# MB_CPU_memory.net
KiCad netlist of a schematic drawn in Altium Designer
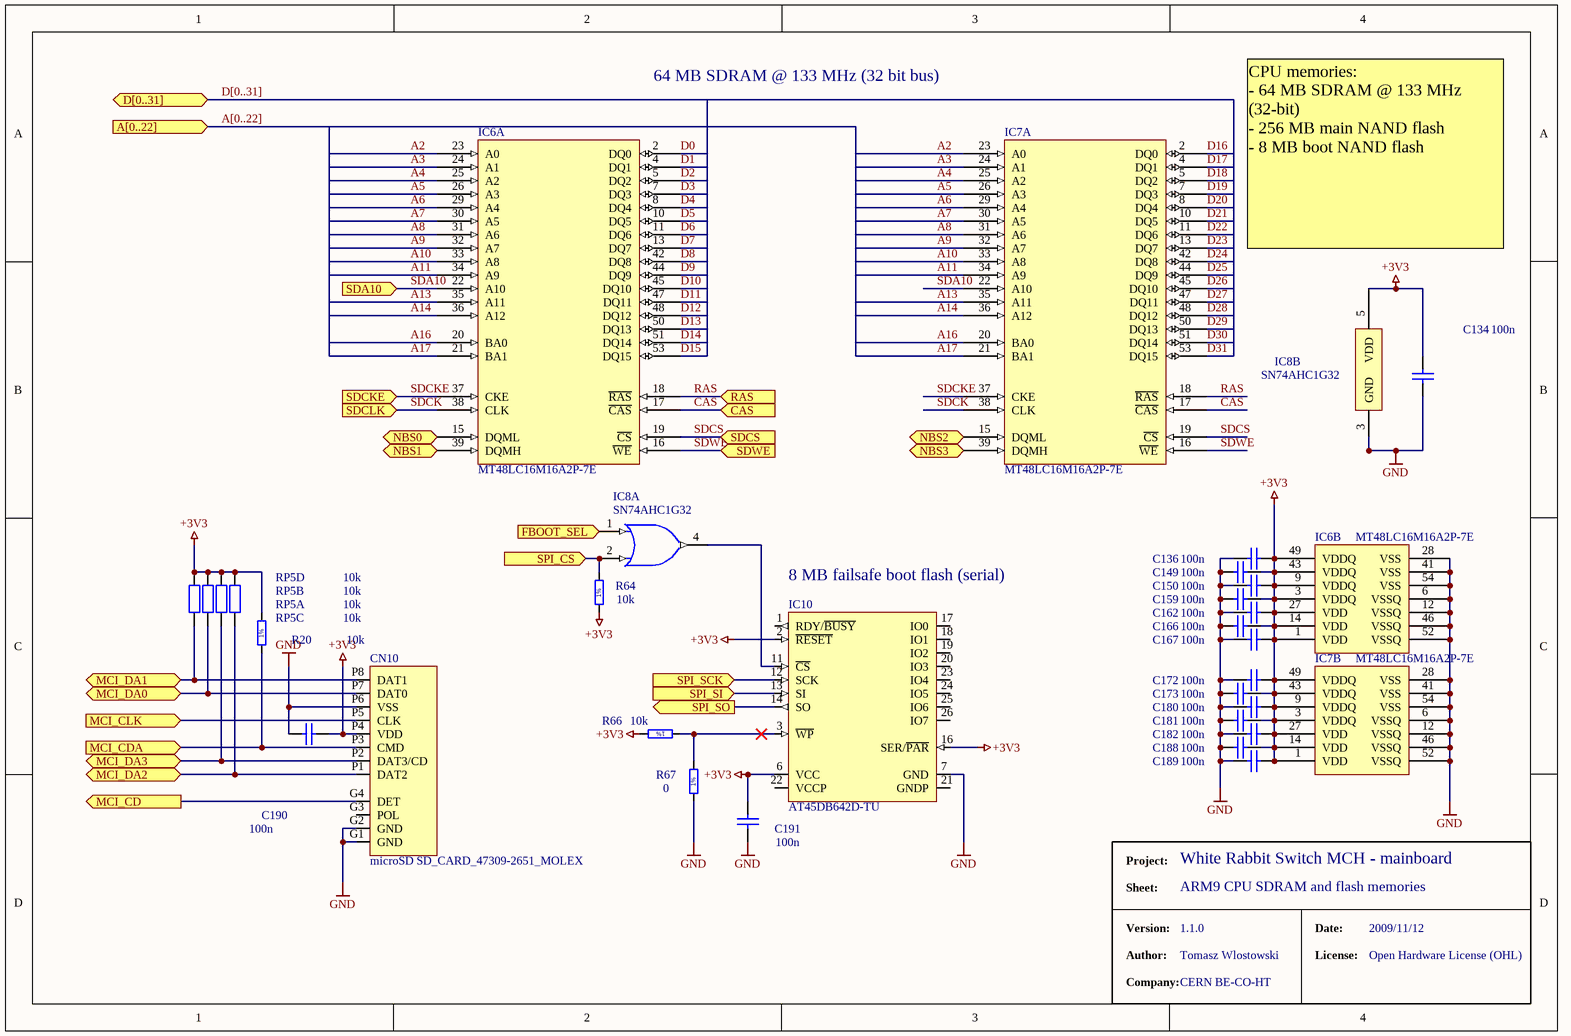
[diagram p0: MB_CPU_memory.SchDoc]

(export (version "E")
  (design (tool "Eeschema 10.0.6"))
  (components
    (comp (ref "C134")
      (value "100n")
      (footprint "CAPC1005X55N")
      (description "Non-polarised capacitor")
      (fields
        (field (name "PART NUMBER") "CC0402_100NF_16V_10%_X7R")
        (field (name "VOLTAGE") "16V")
        (field (name "AUTHOR") "CERN DEM JLC")
      )
      (libsource (lib "Capacitors") (part "Capacitor - non polarized"))
    )
    (comp (ref "C136")
      (value "100n")
      (footprint "CAPC1005X55N")
      (description "Non-polarised capacitor")
      (fields
        (field (name "PART NUMBER") "CC0402_100NF_16V_10%_X7R")
        (field (name "VOLTAGE") "16V")
        (field (name "AUTHOR") "CERN DEM JLC")
      )
      (libsource (lib "Capacitors") (part "Capacitor - non polarized"))
    )
    (comp (ref "C149")
      (value "100n")
      (footprint "CAPC1005X55N")
      (description "Non-polarised capacitor")
      (fields
        (field (name "PART NUMBER") "CC0402_100NF_16V_10%_X7R")
        (field (name "VOLTAGE") "16V")
        (field (name "AUTHOR") "CERN DEM JLC")
      )
      (libsource (lib "Capacitors") (part "Capacitor - non polarized"))
    )
    (comp (ref "C150")
      (value "100n")
      (footprint "CAPC1005X55N")
      (description "Non-polarised capacitor")
      (fields
        (field (name "PART NUMBER") "CC0402_100NF_16V_10%_X7R")
        (field (name "VOLTAGE") "16V")
        (field (name "AUTHOR") "CERN DEM JLC")
      )
      (libsource (lib "Capacitors") (part "Capacitor - non polarized"))
    )
    (comp (ref "C159")
      (value "100n")
      (footprint "CAPC1005X55N")
      (description "Non-polarised capacitor")
      (fields
        (field (name "PART NUMBER") "CC0402_100NF_16V_10%_X7R")
        (field (name "VOLTAGE") "16V")
        (field (name "AUTHOR") "CERN DEM JLC")
      )
      (libsource (lib "Capacitors") (part "Capacitor - non polarized"))
    )
    (comp (ref "C162")
      (value "100n")
      (footprint "CAPC1005X55N")
      (description "Non-polarised capacitor")
      (fields
        (field (name "PART NUMBER") "CC0402_100NF_16V_10%_X7R")
        (field (name "VOLTAGE") "16V")
        (field (name "AUTHOR") "CERN DEM JLC")
      )
      (libsource (lib "Capacitors") (part "Capacitor - non polarized"))
    )
    (comp (ref "C166")
      (value "100n")
      (footprint "CAPC1005X55N")
      (description "Non-polarised capacitor")
      (fields
        (field (name "PART NUMBER") "CC0402_100NF_16V_10%_X7R")
        (field (name "VOLTAGE") "16V")
        (field (name "AUTHOR") "CERN DEM JLC")
      )
      (libsource (lib "Capacitors") (part "Capacitor - non polarized"))
    )
    (comp (ref "C167")
      (value "100n")
      (footprint "CAPC1005X55N")
      (description "Non-polarised capacitor")
      (fields
        (field (name "PART NUMBER") "CC0402_100NF_16V_10%_X7R")
        (field (name "VOLTAGE") "16V")
        (field (name "AUTHOR") "CERN DEM JLC")
      )
      (libsource (lib "Capacitors") (part "Capacitor - non polarized"))
    )
    (comp (ref "C172")
      (value "100n")
      (footprint "CAPC1005X55N")
      (description "Non-polarised capacitor")
      (fields
        (field (name "PART NUMBER") "CC0402_100NF_16V_10%_X7R")
        (field (name "VOLTAGE") "16V")
        (field (name "AUTHOR") "CERN DEM JLC")
      )
      (libsource (lib "Capacitors") (part "Capacitor - non polarized"))
    )
    (comp (ref "C173")
      (value "100n")
      (footprint "CAPC1005X55N")
      (description "Non-polarised capacitor")
      (fields
        (field (name "PART NUMBER") "CC0402_100NF_16V_10%_X7R")
        (field (name "VOLTAGE") "16V")
        (field (name "AUTHOR") "CERN DEM JLC")
      )
      (libsource (lib "Capacitors") (part "Capacitor - non polarized"))
    )
    (comp (ref "C180")
      (value "100n")
      (footprint "CAPC1005X55N")
      (description "Non-polarised capacitor")
      (fields
        (field (name "PART NUMBER") "CC0402_100NF_16V_10%_X7R")
        (field (name "VOLTAGE") "16V")
        (field (name "AUTHOR") "CERN DEM JLC")
      )
      (libsource (lib "Capacitors") (part "Capacitor - non polarized"))
    )
    (comp (ref "C181")
      (value "100n")
      (footprint "CAPC1005X55N")
      (description "Non-polarised capacitor")
      (fields
        (field (name "PART NUMBER") "CC0402_100NF_16V_10%_X7R")
        (field (name "VOLTAGE") "16V")
        (field (name "AUTHOR") "CERN DEM JLC")
      )
      (libsource (lib "Capacitors") (part "Capacitor - non polarized"))
    )
    (comp (ref "C182")
      (value "100n")
      (footprint "CAPC1005X55N")
      (description "Non-polarised capacitor")
      (fields
        (field (name "PART NUMBER") "CC0402_100NF_16V_10%_X7R")
        (field (name "VOLTAGE") "16V")
        (field (name "AUTHOR") "CERN DEM JLC")
      )
      (libsource (lib "Capacitors") (part "Capacitor - non polarized"))
    )
    (comp (ref "C188")
      (value "100n")
      (footprint "CAPC1005X55N")
      (description "Non-polarised capacitor")
      (fields
        (field (name "PART NUMBER") "CC0402_100NF_16V_10%_X7R")
        (field (name "VOLTAGE") "16V")
        (field (name "AUTHOR") "CERN DEM JLC")
      )
      (libsource (lib "Capacitors") (part "Capacitor - non polarized"))
    )
    (comp (ref "C189")
      (value "100n")
      (footprint "CAPC1005X55N")
      (description "Non-polarised capacitor")
      (fields
        (field (name "PART NUMBER") "CC0402_100NF_16V_10%_X7R")
        (field (name "VOLTAGE") "16V")
        (field (name "AUTHOR") "CERN DEM JLC")
      )
      (libsource (lib "Capacitors") (part "Capacitor - non polarized"))
    )
    (comp (ref "C190")
      (value "100n")
      (footprint "CAPC1005X55N")
      (description "Non-polarised capacitor")
      (fields
        (field (name "PART NUMBER") "CC0402_100NF_16V_10%_X7R")
        (field (name "VOLTAGE") "16V")
        (field (name "AUTHOR") "CERN DEM JLC")
      )
      (libsource (lib "Capacitors") (part "Capacitor - non polarized"))
    )
    (comp (ref "C191")
      (value "100n")
      (footprint "CAPC1005X55N")
      (description "Non-polarised capacitor")
      (fields
        (field (name "PART NUMBER") "CC0402_100NF_16V_10%_X7R")
        (field (name "VOLTAGE") "16V")
        (field (name "AUTHOR") "CERN DEM JLC")
      )
      (libsource (lib "Capacitors") (part "Capacitor - non polarized"))
    )
    (comp (ref "CN10")
      (value "microSD SD_CARD_47309-2651_MOLEX")
      (footprint "SD_CARD_47309-2651_MOLEX")
      (description "Secure Digital Cards socket (Farnell)")
      (libsource (lib "LIBRARY_SCH") (part "CON_CARD_micro_SD"))
    )
    (comp (ref "IC6")
      (value "MT48LC16M16A2P-7E")
      (footprint "TSOP54")
      (description "Micron 256Mbit PC133 SDRAM w/16-bit data bus")
      (fields (field (name "Comment") "MT48LC16M16A2TG"))
      (libsource (lib "wr_switch") (part "MT48LC16M16A2TG"))
    )
    (comp (ref "IC7")
      (value "MT48LC16M16A2P-7E")
      (footprint "TSOP54")
      (description "Micron 256Mbit PC133 SDRAM w/16-bit data bus")
      (fields (field (name "Comment") "MT48LC16M16A2TG"))
      (libsource (lib "wr_switch") (part "MT48LC16M16A2TG"))
    )
    (comp (ref "IC8")
      (value "SN74AHC1G32")
      (footprint "SOT23-5AL")
      (description "TI single OR gate")
      (libsource (lib "wr_switch") (part "SN74AHC1G32"))
    )
    (comp (ref "IC10")
      (value "AT45DB642D-TU")
      (footprint "TSOP28-1")
      (description "serial data FLASH")
      (fields (field (name "Comment") "AT45DB642"))
      (libsource (lib "wr_switch") (part "MEM_AT45DB642"))
    )
    (comp (ref "R20")
      (value "10k")
      (footprint "RESC1608X55N")
      (description "Resistor - 1%")
      (fields
        (field (name "PART NUMBER") "R0603_10K_1%_0.1W_100PPM")
        (field (name "POWER") "0.1W")
        (field (name "AUTHOR") "CERN DEM JLC")
      )
      (libsource (lib "Resistors") (part "Resistor - 1%"))
    )
    (comp (ref "R64")
      (value "10k")
      (footprint "RESC1005X40N")
      (description "Resistor - 1%")
      (fields
        (field (name "PART NUMBER") "R0402_10K_1%_0.0625W_100PPM")
        (field (name "POWER") "0.0625W")
        (field (name "AUTHOR") "CERN DEM JLC")
      )
      (libsource (lib "Resistors") (part "Resistor - 1%"))
    )
    (comp (ref "R66")
      (value "10k")
      (footprint "RESC1005X40N")
      (description "Resistor - 1%")
      (fields
        (field (name "PART NUMBER") "R0402_10K_1%_0.0625W_100PPM")
        (field (name "POWER") "0.0625W")
        (field (name "AUTHOR") "CERN DEM JLC")
      )
      (libsource (lib "Resistors") (part "Resistor - 1%"))
    )
    (comp (ref "R67")
      (value "0")
      (footprint "RESC1005X40N")
      (description "Resistor - 1%")
      (fields
        (field (name "PART NUMBER") "R0402_0R_JUMPER")
        (field (name "MANUFACTURER") "GENERIC")
        (field (name "AUTHOR") "CERN DEM JLC")
      )
      (libsource (lib "Resistors") (part "Resistor - 1%"))
    )
    (comp (ref "RP5")
      (value "10k")
      (footprint "YC124")
      (description "4-resistor pack")
      (fields (field (name "Comment") "10k 0804"))
      (libsource (lib "wr_switch") (part "Res_Pack4_10k_YC124"))
    )
  )
  (nets
    (net (code "10") (name "+3V3") (class "Default")
      (node (ref "C134") (pin "1") (pinfunction "1_1") (pintype "passive"))
      (node (ref "C136") (pin "2") (pinfunction "2_2") (pintype "passive"))
      (node (ref "C149") (pin "2") (pinfunction "2_2") (pintype "passive"))
      (node (ref "C150") (pin "2") (pinfunction "2_2") (pintype "passive"))
      (node (ref "C159") (pin "2") (pinfunction "2_2") (pintype "passive"))
      (node (ref "C162") (pin "2") (pinfunction "2_2") (pintype "passive"))
      (node (ref "C166") (pin "2") (pinfunction "2_2") (pintype "passive"))
      (node (ref "C167") (pin "2") (pinfunction "2_2") (pintype "passive"))
      (node (ref "C172") (pin "2") (pinfunction "2_2") (pintype "passive"))
      (node (ref "C173") (pin "2") (pinfunction "2_2") (pintype "passive"))
      (node (ref "C180") (pin "2") (pinfunction "2_2") (pintype "passive"))
      (node (ref "C181") (pin "2") (pinfunction "2_2") (pintype "passive"))
      (node (ref "C182") (pin "2") (pinfunction "2_2") (pintype "passive"))
      (node (ref "C188") (pin "2") (pinfunction "2_2") (pintype "passive"))
      (node (ref "C189") (pin "2") (pinfunction "2_2") (pintype "passive"))
      (node (ref "C190") (pin "2") (pinfunction "2_2") (pintype "passive"))
      (node (ref "C191") (pin "2") (pinfunction "2_2") (pintype "passive"))
      (node (ref "CN10") (pin "P4") (pinfunction "VDD_P4") (pintype "passive"))
      (node (ref "IC10") (pin "16") (pinfunction "SER/~{PAR}_16") (pintype "input"))
      (node (ref "IC10") (pin "2") (pinfunction "~{RESET}_2") (pintype "input"))
      (node (ref "IC10") (pin "6") (pinfunction "VCC_6") (pintype "power_in"))
      (node (ref "IC6") (pin "1") (pinfunction "VDD_1") (pintype "power_in"))
      (node (ref "IC6") (pin "14") (pinfunction "VDD_14") (pintype "power_in"))
      (node (ref "IC6") (pin "27") (pinfunction "VDD_27") (pintype "power_in"))
      (node (ref "IC6") (pin "3") (pinfunction "VDDQ_3") (pintype "power_in"))
      (node (ref "IC6") (pin "43") (pinfunction "VDDQ_43") (pintype "power_in"))
      (node (ref "IC6") (pin "49") (pinfunction "VDDQ_49") (pintype "power_in"))
      (node (ref "IC6") (pin "9") (pinfunction "VDDQ_9") (pintype "power_in"))
      (node (ref "IC7") (pin "1") (pinfunction "VDD_1") (pintype "power_in"))
      (node (ref "IC7") (pin "14") (pinfunction "VDD_14") (pintype "power_in"))
      (node (ref "IC7") (pin "27") (pinfunction "VDD_27") (pintype "power_in"))
      (node (ref "IC7") (pin "3") (pinfunction "VDDQ_3") (pintype "power_in"))
      (node (ref "IC7") (pin "43") (pinfunction "VDDQ_43") (pintype "power_in"))
      (node (ref "IC7") (pin "49") (pinfunction "VDDQ_49") (pintype "power_in"))
      (node (ref "IC7") (pin "9") (pinfunction "VDDQ_9") (pintype "power_in"))
      (node (ref "IC8") (pin "5") (pinfunction "VDD_5") (pintype "passive"))
      (node (ref "R20") (pin "2") (pinfunction "2_2") (pintype "passive"))
      (node (ref "R64") (pin "1") (pinfunction "1_1") (pintype "passive"))
      (node (ref "R66") (pin "2") (pinfunction "2_2") (pintype "passive"))
      (node (ref "RP5") (pin "5") (pinfunction "B_5") (pintype "passive"))
      (node (ref "RP5") (pin "6") (pinfunction "B_6") (pintype "passive"))
      (node (ref "RP5") (pin "7") (pinfunction "B_7") (pintype "passive"))
      (node (ref "RP5") (pin "8") (pinfunction "B_8") (pintype "passive"))
    )
    (net (code "11") (name "/A2") (class "Default")
      (node (ref "IC6") (pin "23") (pinfunction "A0_23") (pintype "input"))
      (node (ref "IC7") (pin "23") (pinfunction "A0_23") (pintype "input"))
    )
    (net (code "12") (name "/A3") (class "Default")
      (node (ref "IC6") (pin "24") (pinfunction "A1_24") (pintype "input"))
      (node (ref "IC7") (pin "24") (pinfunction "A1_24") (pintype "input"))
    )
    (net (code "13") (name "/A4") (class "Default")
      (node (ref "IC6") (pin "25") (pinfunction "A2_25") (pintype "input"))
      (node (ref "IC7") (pin "25") (pinfunction "A2_25") (pintype "input"))
    )
    (net (code "14") (name "/A5") (class "Default")
      (node (ref "IC6") (pin "26") (pinfunction "A3_26") (pintype "input"))
      (node (ref "IC7") (pin "26") (pinfunction "A3_26") (pintype "input"))
    )
    (net (code "15") (name "/A6") (class "Default")
      (node (ref "IC6") (pin "29") (pinfunction "A4_29") (pintype "input"))
      (node (ref "IC7") (pin "29") (pinfunction "A4_29") (pintype "input"))
    )
    (net (code "16") (name "/A7") (class "Default")
      (node (ref "IC6") (pin "30") (pinfunction "A5_30") (pintype "input"))
      (node (ref "IC7") (pin "30") (pinfunction "A5_30") (pintype "input"))
    )
    (net (code "17") (name "/A8") (class "Default")
      (node (ref "IC6") (pin "31") (pinfunction "A6_31") (pintype "input"))
      (node (ref "IC7") (pin "31") (pinfunction "A6_31") (pintype "input"))
    )
    (net (code "18") (name "/A9") (class "Default")
      (node (ref "IC6") (pin "32") (pinfunction "A7_32") (pintype "input"))
      (node (ref "IC7") (pin "32") (pinfunction "A7_32") (pintype "input"))
    )
    (net (code "19") (name "/A10") (class "Default")
      (node (ref "IC6") (pin "33") (pinfunction "A8_33") (pintype "input"))
      (node (ref "IC7") (pin "33") (pinfunction "A8_33") (pintype "input"))
    )
    (net (code "20") (name "/A11") (class "Default")
      (node (ref "IC6") (pin "34") (pinfunction "A9_34") (pintype "input"))
      (node (ref "IC7") (pin "34") (pinfunction "A9_34") (pintype "input"))
    )
    (net (code "21") (name "/A13") (class "Default")
      (node (ref "IC6") (pin "35") (pinfunction "A11_35") (pintype "input"))
      (node (ref "IC7") (pin "35") (pinfunction "A11_35") (pintype "input"))
    )
    (net (code "22") (name "/A14") (class "Default")
      (node (ref "IC6") (pin "36") (pinfunction "A12_36") (pintype "input"))
      (node (ref "IC7") (pin "36") (pinfunction "A12_36") (pintype "input"))
    )
    (net (code "23") (name "/A16") (class "Default")
      (node (ref "IC6") (pin "20") (pinfunction "BA0_20") (pintype "input"))
      (node (ref "IC7") (pin "20") (pinfunction "BA0_20") (pintype "input"))
    )
    (net (code "24") (name "/A17") (class "Default")
      (node (ref "IC6") (pin "21") (pinfunction "BA1_21") (pintype "input"))
      (node (ref "IC7") (pin "21") (pinfunction "BA1_21") (pintype "input"))
    )
    (net (code "26") (name "/CAS") (class "Default")
      (node (ref "IC6") (pin "17") (pinfunction "~{CAS}_17") (pintype "input"))
      (node (ref "IC7") (pin "17") (pinfunction "~{CAS}_17") (pintype "input"))
    )
    (net (code "27") (name "/D0") (class "Default")
      (node (ref "IC6") (pin "2") (pinfunction "DQ0_2") (pintype "bidirectional"))
    )
    (net (code "28") (name "/D1") (class "Default")
      (node (ref "IC6") (pin "4") (pinfunction "DQ1_4") (pintype "bidirectional"))
    )
    (net (code "29") (name "/D2") (class "Default")
      (node (ref "IC6") (pin "5") (pinfunction "DQ2_5") (pintype "bidirectional"))
    )
    (net (code "30") (name "/D3") (class "Default")
      (node (ref "IC6") (pin "7") (pinfunction "DQ3_7") (pintype "bidirectional"))
    )
    (net (code "31") (name "/D4") (class "Default")
      (node (ref "IC6") (pin "8") (pinfunction "DQ4_8") (pintype "bidirectional"))
    )
    (net (code "32") (name "/D5") (class "Default")
      (node (ref "IC6") (pin "10") (pinfunction "DQ5_10") (pintype "bidirectional"))
    )
    (net (code "33") (name "/D6") (class "Default")
      (node (ref "IC6") (pin "11") (pinfunction "DQ6_11") (pintype "bidirectional"))
    )
    (net (code "34") (name "/D7") (class "Default")
      (node (ref "IC6") (pin "13") (pinfunction "DQ7_13") (pintype "bidirectional"))
    )
    (net (code "35") (name "/D8") (class "Default")
      (node (ref "IC6") (pin "42") (pinfunction "DQ8_42") (pintype "bidirectional"))
    )
    (net (code "36") (name "/D9") (class "Default")
      (node (ref "IC6") (pin "44") (pinfunction "DQ9_44") (pintype "bidirectional"))
    )
    (net (code "37") (name "/D10") (class "Default")
      (node (ref "IC6") (pin "45") (pinfunction "DQ10_45") (pintype "bidirectional"))
    )
    (net (code "38") (name "/D11") (class "Default")
      (node (ref "IC6") (pin "47") (pinfunction "DQ11_47") (pintype "bidirectional"))
    )
    (net (code "39") (name "/D12") (class "Default")
      (node (ref "IC6") (pin "48") (pinfunction "DQ12_48") (pintype "bidirectional"))
    )
    (net (code "40") (name "/D13") (class "Default")
      (node (ref "IC6") (pin "50") (pinfunction "DQ13_50") (pintype "bidirectional"))
    )
    (net (code "41") (name "/D14") (class "Default")
      (node (ref "IC6") (pin "51") (pinfunction "DQ14_51") (pintype "bidirectional"))
    )
    (net (code "42") (name "/D15") (class "Default")
      (node (ref "IC6") (pin "53") (pinfunction "DQ15_53") (pintype "bidirectional"))
    )
    (net (code "43") (name "/D16") (class "Default")
      (node (ref "IC7") (pin "2") (pinfunction "DQ0_2") (pintype "bidirectional"))
    )
    (net (code "44") (name "/D17") (class "Default")
      (node (ref "IC7") (pin "4") (pinfunction "DQ1_4") (pintype "bidirectional"))
    )
    (net (code "45") (name "/D18") (class "Default")
      (node (ref "IC7") (pin "5") (pinfunction "DQ2_5") (pintype "bidirectional"))
    )
    (net (code "46") (name "/D19") (class "Default")
      (node (ref "IC7") (pin "7") (pinfunction "DQ3_7") (pintype "bidirectional"))
    )
    (net (code "47") (name "/D20") (class "Default")
      (node (ref "IC7") (pin "8") (pinfunction "DQ4_8") (pintype "bidirectional"))
    )
    (net (code "48") (name "/D21") (class "Default")
      (node (ref "IC7") (pin "10") (pinfunction "DQ5_10") (pintype "bidirectional"))
    )
    (net (code "49") (name "/D22") (class "Default")
      (node (ref "IC7") (pin "11") (pinfunction "DQ6_11") (pintype "bidirectional"))
    )
    (net (code "50") (name "/D23") (class "Default")
      (node (ref "IC7") (pin "13") (pinfunction "DQ7_13") (pintype "bidirectional"))
    )
    (net (code "51") (name "/D24") (class "Default")
      (node (ref "IC7") (pin "42") (pinfunction "DQ8_42") (pintype "bidirectional"))
    )
    (net (code "52") (name "/D25") (class "Default")
      (node (ref "IC7") (pin "44") (pinfunction "DQ9_44") (pintype "bidirectional"))
    )
    (net (code "53") (name "/D26") (class "Default")
      (node (ref "IC7") (pin "45") (pinfunction "DQ10_45") (pintype "bidirectional"))
    )
    (net (code "54") (name "/D27") (class "Default")
      (node (ref "IC7") (pin "47") (pinfunction "DQ11_47") (pintype "bidirectional"))
    )
    (net (code "55") (name "/D28") (class "Default")
      (node (ref "IC7") (pin "48") (pinfunction "DQ12_48") (pintype "bidirectional"))
    )
    (net (code "56") (name "/D29") (class "Default")
      (node (ref "IC7") (pin "50") (pinfunction "DQ13_50") (pintype "bidirectional"))
    )
    (net (code "57") (name "/D30") (class "Default")
      (node (ref "IC7") (pin "51") (pinfunction "DQ14_51") (pintype "bidirectional"))
    )
    (net (code "58") (name "/D31") (class "Default")
      (node (ref "IC7") (pin "53") (pinfunction "DQ15_53") (pintype "bidirectional"))
    )
    (net (code "60") (name "/FBOOT_SEL") (class "Default")
      (node (ref "IC8") (pin "1") (pinfunction "A_1") (pintype "input"))
    )
    (net (code "61") (name "/MCI_CD") (class "Default")
      (node (ref "CN10") (pin "G4") (pinfunction "DET_G4") (pintype "passive"))
    )
    (net (code "62") (name "/MCI_CDA") (class "Default")
      (node (ref "CN10") (pin "P3") (pinfunction "CMD_P3") (pintype "passive"))
      (node (ref "R20") (pin "1") (pinfunction "1_1") (pintype "passive"))
    )
    (net (code "63") (name "/MCI_CLK") (class "Default")
      (node (ref "CN10") (pin "P5") (pinfunction "CLK_P5") (pintype "passive"))
    )
    (net (code "64") (name "/MCI_DA0") (class "Default")
      (node (ref "CN10") (pin "P7") (pinfunction "DAT0_P7") (pintype "passive"))
      (node (ref "RP5") (pin "2") (pinfunction "A_2") (pintype "passive"))
    )
    (net (code "65") (name "/MCI_DA1") (class "Default")
      (node (ref "CN10") (pin "P8") (pinfunction "DAT1_P8") (pintype "passive"))
      (node (ref "RP5") (pin "4") (pinfunction "A_4") (pintype "passive"))
    )
    (net (code "66") (name "/MCI_DA2") (class "Default")
      (node (ref "CN10") (pin "P1") (pinfunction "DAT2_P1") (pintype "passive"))
      (node (ref "RP5") (pin "1") (pinfunction "A_1") (pintype "passive"))
    )
    (net (code "67") (name "/MCI_DA3") (class "Default")
      (node (ref "CN10") (pin "P2") (pinfunction "DAT3/CD_P2") (pintype "passive"))
      (node (ref "RP5") (pin "3") (pinfunction "A_3") (pintype "passive"))
    )
    (net (code "68") (name "/NBS0") (class "Default")
      (node (ref "IC6") (pin "15") (pinfunction "DQML_15") (pintype "input"))
    )
    (net (code "69") (name "/NBS1") (class "Default")
      (node (ref "IC6") (pin "39") (pinfunction "DQMH_39") (pintype "input"))
    )
    (net (code "70") (name "/NBS2") (class "Default")
      (node (ref "IC7") (pin "15") (pinfunction "DQML_15") (pintype "input"))
    )
    (net (code "71") (name "/NBS3") (class "Default")
      (node (ref "IC7") (pin "39") (pinfunction "DQMH_39") (pintype "input"))
    )
    (net (code "72") (name "/RAS") (class "Default")
      (node (ref "IC6") (pin "18") (pinfunction "~{RAS}_18") (pintype "input"))
      (node (ref "IC7") (pin "18") (pinfunction "~{RAS}_18") (pintype "input"))
    )
    (net (code "73") (name "/SDA10") (class "Default")
      (node (ref "IC6") (pin "22") (pinfunction "A10_22") (pintype "input"))
      (node (ref "IC7") (pin "22") (pinfunction "A10_22") (pintype "input"))
    )
    (net (code "74") (name "/SDCK") (class "Default")
      (node (ref "IC6") (pin "38") (pinfunction "CLK_38") (pintype "input"))
      (node (ref "IC7") (pin "38") (pinfunction "CLK_38") (pintype "input"))
    )
    (net (code "75") (name "/SDCKE") (class "Default")
      (node (ref "IC6") (pin "37") (pinfunction "CKE_37") (pintype "input"))
      (node (ref "IC7") (pin "37") (pinfunction "CKE_37") (pintype "input"))
    )
    (net (code "76") (name "/SDCS") (class "Default")
      (node (ref "IC6") (pin "19") (pinfunction "~{CS}_19") (pintype "input"))
      (node (ref "IC7") (pin "19") (pinfunction "~{CS}_19") (pintype "input"))
    )
    (net (code "77") (name "/SDWE") (class "Default")
      (node (ref "IC6") (pin "16") (pinfunction "~{WE}_16") (pintype "input"))
      (node (ref "IC7") (pin "16") (pinfunction "~{WE}_16") (pintype "input"))
    )
    (net (code "78") (name "/SPI_CS") (class "Default")
      (node (ref "IC8") (pin "2") (pinfunction "B_2") (pintype "input"))
      (node (ref "R64") (pin "2") (pinfunction "2_2") (pintype "passive"))
    )
    (net (code "79") (name "/SPI_SCK") (class "Default")
      (node (ref "IC10") (pin "12") (pinfunction "SCK_12") (pintype "input"))
    )
    (net (code "80") (name "/SPI_SI") (class "Default")
      (node (ref "IC10") (pin "13") (pinfunction "SI_13") (pintype "input"))
    )
    (net (code "81") (name "/SPI_SO") (class "Default")
      (node (ref "IC10") (pin "14") (pinfunction "SO_14") (pintype "output"))
    )
    (net (code "82") (name "GND") (class "Default")
      (node (ref "C134") (pin "2") (pinfunction "2_2") (pintype "passive"))
      (node (ref "C136") (pin "1") (pinfunction "1_1") (pintype "passive"))
      (node (ref "C149") (pin "1") (pinfunction "1_1") (pintype "passive"))
      (node (ref "C150") (pin "1") (pinfunction "1_1") (pintype "passive"))
      (node (ref "C159") (pin "1") (pinfunction "1_1") (pintype "passive"))
      (node (ref "C162") (pin "1") (pinfunction "1_1") (pintype "passive"))
      (node (ref "C166") (pin "1") (pinfunction "1_1") (pintype "passive"))
      (node (ref "C167") (pin "1") (pinfunction "1_1") (pintype "passive"))
      (node (ref "C172") (pin "1") (pinfunction "1_1") (pintype "passive"))
      (node (ref "C173") (pin "1") (pinfunction "1_1") (pintype "passive"))
      (node (ref "C180") (pin "1") (pinfunction "1_1") (pintype "passive"))
      (node (ref "C181") (pin "1") (pinfunction "1_1") (pintype "passive"))
      (node (ref "C182") (pin "1") (pinfunction "1_1") (pintype "passive"))
      (node (ref "C188") (pin "1") (pinfunction "1_1") (pintype "passive"))
      (node (ref "C189") (pin "1") (pinfunction "1_1") (pintype "passive"))
      (node (ref "C190") (pin "1") (pinfunction "1_1") (pintype "passive"))
      (node (ref "C191") (pin "1") (pinfunction "1_1") (pintype "passive"))
      (node (ref "CN10") (pin "G1") (pinfunction "GND_G1") (pintype "passive"))
      (node (ref "CN10") (pin "G2") (pinfunction "GND_G2") (pintype "passive"))
      (node (ref "CN10") (pin "P6") (pinfunction "VSS_P6") (pintype "passive"))
      (node (ref "IC10") (pin "7") (pinfunction "GND_7") (pintype "power_in"))
      (node (ref "IC6") (pin "12") (pinfunction "VSSQ_12") (pintype "power_in"))
      (node (ref "IC6") (pin "28") (pinfunction "VSS_28") (pintype "power_in"))
      (node (ref "IC6") (pin "41") (pinfunction "VSS_41") (pintype "power_in"))
      (node (ref "IC6") (pin "46") (pinfunction "VSSQ_46") (pintype "power_in"))
      (node (ref "IC6") (pin "52") (pinfunction "VSSQ_52") (pintype "power_in"))
      (node (ref "IC6") (pin "54") (pinfunction "VSS_54") (pintype "power_in"))
      (node (ref "IC6") (pin "6") (pinfunction "VSSQ_6") (pintype "power_in"))
      (node (ref "IC7") (pin "12") (pinfunction "VSSQ_12") (pintype "power_in"))
      (node (ref "IC7") (pin "28") (pinfunction "VSS_28") (pintype "power_in"))
      (node (ref "IC7") (pin "41") (pinfunction "VSS_41") (pintype "power_in"))
      (node (ref "IC7") (pin "46") (pinfunction "VSSQ_46") (pintype "power_in"))
      (node (ref "IC7") (pin "52") (pinfunction "VSSQ_52") (pintype "power_in"))
      (node (ref "IC7") (pin "54") (pinfunction "VSS_54") (pintype "power_in"))
      (node (ref "IC7") (pin "6") (pinfunction "VSSQ_6") (pintype "power_in"))
      (node (ref "IC8") (pin "3") (pinfunction "GND_3") (pintype "passive"))
      (node (ref "R67") (pin "1") (pinfunction "1_1") (pintype "passive"))
    )
    (net (code "83") (name "Net-(IC10-~{CS})") (class "Default")
      (node (ref "IC10") (pin "11") (pinfunction "~{CS}_11") (pintype "input"))
      (node (ref "IC8") (pin "4") (pinfunction "Y_4") (pintype "output"))
    )
    (net (code "84") (name "Net-(IC10-~{WP})") (class "Default")
      (node (ref "IC10") (pin "3") (pinfunction "~{WP}_3") (pintype "input"))
      (node (ref "R66") (pin "1") (pinfunction "1_1") (pintype "passive"))
      (node (ref "R67") (pin "2") (pinfunction "2_2") (pintype "passive"))
    )
    (net (code "85") (name "unconnected-(CN10-POL-PadG3)") (class "Default")
      (node (ref "CN10") (pin "G3") (pinfunction "POL_G3") (pintype "passive"))
    )
    (net (code "86") (name "unconnected-(IC10-GNDP-Pad21)") (class "Default")
      (node (ref "IC10") (pin "21") (pinfunction "GNDP_21") (pintype "power_in"))
    )
    (net (code "87") (name "unconnected-(IC10-IO0-Pad17)") (class "Default")
      (node (ref "IC10") (pin "17") (pinfunction "IO0_17") (pintype "bidirectional"))
    )
    (net (code "88") (name "unconnected-(IC10-IO1-Pad18)") (class "Default")
      (node (ref "IC10") (pin "18") (pinfunction "IO1_18") (pintype "bidirectional"))
    )
    (net (code "89") (name "unconnected-(IC10-IO2-Pad19)") (class "Default")
      (node (ref "IC10") (pin "19") (pinfunction "IO2_19") (pintype "bidirectional"))
    )
    (net (code "90") (name "unconnected-(IC10-IO3-Pad20)") (class "Default")
      (node (ref "IC10") (pin "20") (pinfunction "IO3_20") (pintype "bidirectional"))
    )
    (net (code "91") (name "unconnected-(IC10-IO4-Pad23)") (class "Default")
      (node (ref "IC10") (pin "23") (pinfunction "IO4_23") (pintype "bidirectional"))
    )
    (net (code "92") (name "unconnected-(IC10-IO5-Pad24)") (class "Default")
      (node (ref "IC10") (pin "24") (pinfunction "IO5_24") (pintype "bidirectional"))
    )
    (net (code "93") (name "unconnected-(IC10-IO6-Pad25)") (class "Default")
      (node (ref "IC10") (pin "25") (pinfunction "IO6_25") (pintype "bidirectional"))
    )
    (net (code "94") (name "unconnected-(IC10-IO7-Pad26)") (class "Default")
      (node (ref "IC10") (pin "26") (pinfunction "IO7_26") (pintype "bidirectional"))
    )
    (net (code "95") (name "unconnected-(IC10-RDY{slash}~{BUSY}-Pad1)") (class "Default")
      (node (ref "IC10") (pin "1") (pinfunction "RDY/~{BUSY}_1") (pintype "output"))
    )
    (net (code "96") (name "unconnected-(IC10-VCCP-Pad22)") (class "Default")
      (node (ref "IC10") (pin "22") (pinfunction "VCCP_22") (pintype "power_in"))
    )
  )
)
